# Supplies.net
KiCad netlist of a schematic drawn in Altium Designer
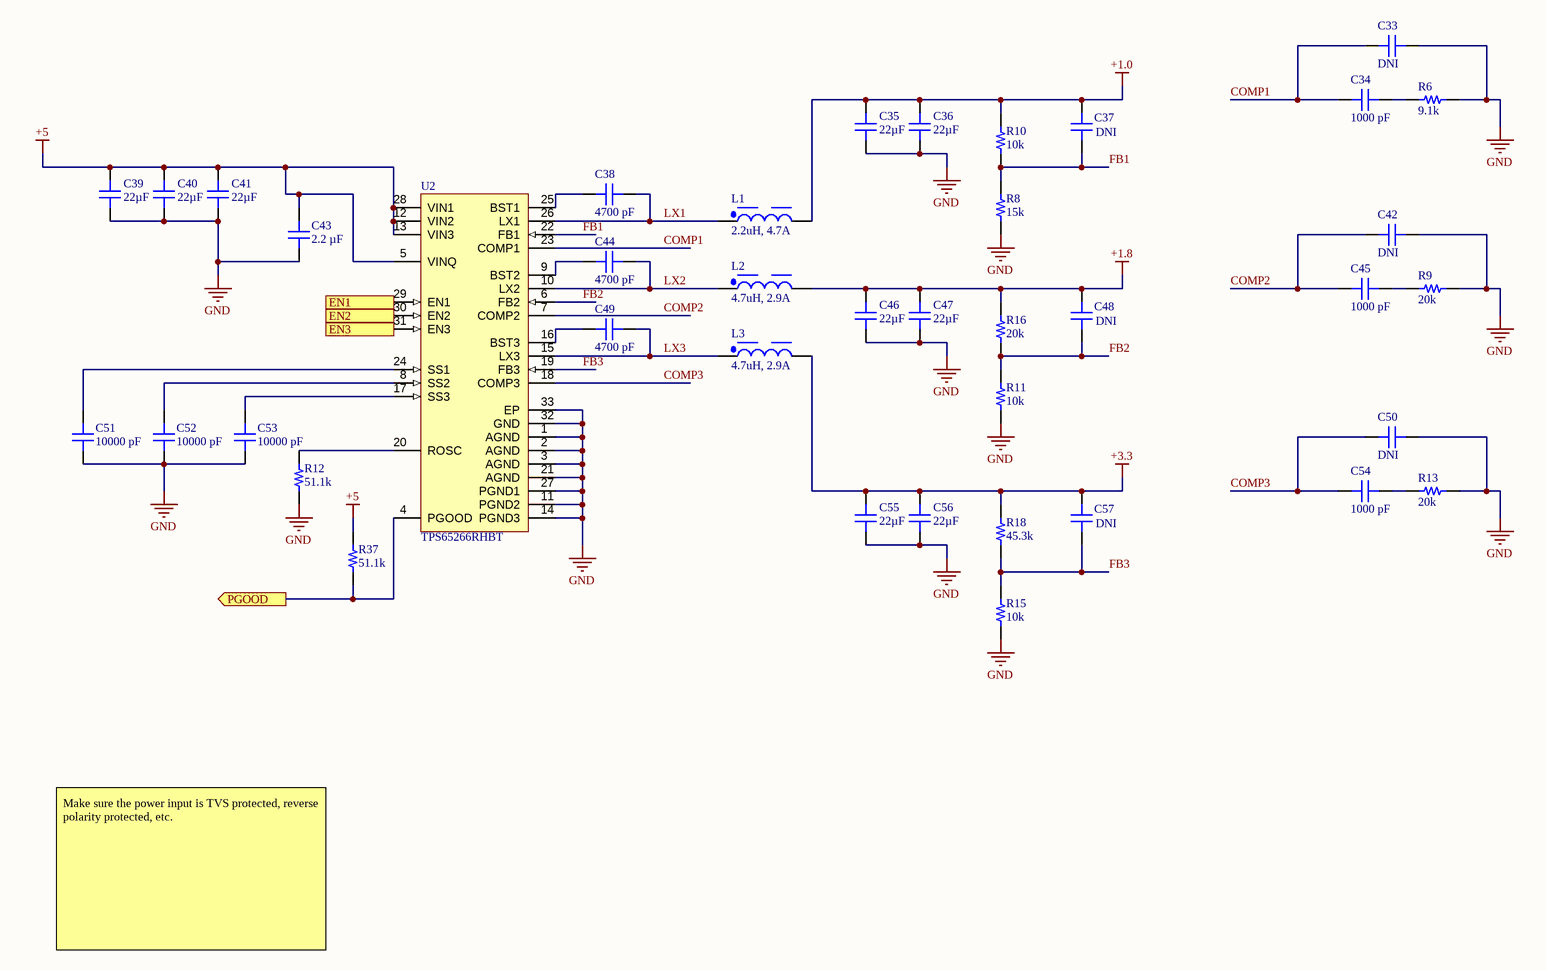
[diagram p0: Supplies.SchDoc]

(export (version "E")
  (design (tool "Eeschema 10.0.6"))
  (components
    (comp (ref "C33")
      (value "DNI")
      (footprint "CAP 0402_1005")
      (libsource (lib "Celestial Altium Library - altium_library") (part "Capacitor"))
    )
    (comp (ref "C34")
      (value "1000 pF")
      (footprint "CAP 0402_1005")
      (description "CAP CER 1000PF 50V C0G/NP0 0402")
      (fields (field (name "PART NUMBER") "C0402C102J5GACAUTO") (field (name "MANUFACTURER") "KEMET"))
      (libsource (lib "Celestial Altium Library - altium_library") (part "Capacitor"))
    )
    (comp (ref "C35")
      (value "22µF")
      (footprint "CAP 0805_2012")
      (description "CAP CER 22UF 10V X5R 0805")
      (fields
        (field (name "PART NUMBER") "GRM21BR61A226ME44L")
        (field (name "MANUFACTURER") "Murata Electronics")
      )
      (libsource (lib "Celestial Altium Library - altium_library") (part "Capacitor"))
    )
    (comp (ref "C36")
      (value "22µF")
      (footprint "CAP 0805_2012")
      (description "CAP CER 22UF 10V X5R 0805")
      (fields
        (field (name "PART NUMBER") "GRM21BR61A226ME44L")
        (field (name "MANUFACTURER") "Murata Electronics")
      )
      (libsource (lib "Celestial Altium Library - altium_library") (part "Capacitor"))
    )
    (comp (ref "C37")
      (value "DNI")
      (footprint "CAP 0402_1005")
      (libsource (lib "Celestial Altium Library - altium_library") (part "Capacitor"))
    )
    (comp (ref "C38")
      (value "4700 pF")
      (footprint "CAP 0201_0603")
      (description "CAP CER 4700PF 16V X7R 0201")
      (fields
        (field (name "PART NUMBER") "GRM033R71C472KE14D")
        (field (name "MANUFACTURER") "Murata Electronics")
      )
      (libsource (lib "Celestial Altium Library - altium_library") (part "Capacitor"))
    )
    (comp (ref "C39")
      (value "22µF")
      (footprint "CAP 0805_2012")
      (description "CAP CER 22UF 10V X5R 0805")
      (fields
        (field (name "PART NUMBER") "GRM21BR61A226ME44L")
        (field (name "MANUFACTURER") "Murata Electronics")
      )
      (libsource (lib "Celestial Altium Library - altium_library") (part "Capacitor"))
    )
    (comp (ref "C40")
      (value "22µF")
      (footprint "CAP 0805_2012")
      (description "CAP CER 22UF 10V X5R 0805")
      (fields
        (field (name "PART NUMBER") "GRM21BR61A226ME44L")
        (field (name "MANUFACTURER") "Murata Electronics")
      )
      (libsource (lib "Celestial Altium Library - altium_library") (part "Capacitor"))
    )
    (comp (ref "C41")
      (value "22µF")
      (footprint "CAP 0805_2012")
      (description "CAP CER 22UF 10V X5R 0805")
      (fields
        (field (name "PART NUMBER") "GRM21BR61A226ME44L")
        (field (name "MANUFACTURER") "Murata Electronics")
      )
      (libsource (lib "Celestial Altium Library - altium_library") (part "Capacitor"))
    )
    (comp (ref "C42")
      (value "DNI")
      (footprint "CAP 0402_1005")
      (libsource (lib "Celestial Altium Library - altium_library") (part "Capacitor"))
    )
    (comp (ref "C43")
      (value "2.2 µF")
      (footprint "CAP 0402_1005")
      (description "CAP CER 2.2UF 16V X5R 0402")
      (fields
        (field (name "PART NUMBER") "GRM155R61C225KE11D")
        (field (name "MANUFACTURER") "Murata Electronics")
      )
      (libsource (lib "Celestial Altium Library - altium_library") (part "Capacitor"))
    )
    (comp (ref "C44")
      (value "4700 pF")
      (footprint "CAP 0201_0603")
      (description "CAP CER 4700PF 16V X7R 0201")
      (fields
        (field (name "PART NUMBER") "GRM033R71C472KE14D")
        (field (name "MANUFACTURER") "Murata Electronics")
      )
      (libsource (lib "Celestial Altium Library - altium_library") (part "Capacitor"))
    )
    (comp (ref "C45")
      (value "1000 pF")
      (footprint "CAP 0402_1005")
      (description "CAP CER 1000PF 50V C0G/NP0 0402")
      (fields (field (name "PART NUMBER") "C0402C102J5GACAUTO") (field (name "MANUFACTURER") "KEMET"))
      (libsource (lib "Celestial Altium Library - altium_library") (part "Capacitor"))
    )
    (comp (ref "C46")
      (value "22µF")
      (footprint "CAP 0805_2012")
      (description "CAP CER 22UF 10V X5R 0805")
      (fields
        (field (name "PART NUMBER") "GRM21BR61A226ME44L")
        (field (name "MANUFACTURER") "Murata Electronics")
      )
      (libsource (lib "Celestial Altium Library - altium_library") (part "Capacitor"))
    )
    (comp (ref "C47")
      (value "22µF")
      (footprint "CAP 0805_2012")
      (description "CAP CER 22UF 10V X5R 0805")
      (fields
        (field (name "PART NUMBER") "GRM21BR61A226ME44L")
        (field (name "MANUFACTURER") "Murata Electronics")
      )
      (libsource (lib "Celestial Altium Library - altium_library") (part "Capacitor"))
    )
    (comp (ref "C48")
      (value "DNI")
      (footprint "CAP 0402_1005")
      (libsource (lib "Celestial Altium Library - altium_library") (part "Capacitor"))
    )
    (comp (ref "C49")
      (value "4700 pF")
      (footprint "CAP 0201_0603")
      (description "CAP CER 4700PF 16V X7R 0201")
      (fields
        (field (name "PART NUMBER") "GRM033R71C472KE14D")
        (field (name "MANUFACTURER") "Murata Electronics")
      )
      (libsource (lib "Celestial Altium Library - altium_library") (part "Capacitor"))
    )
    (comp (ref "C50")
      (value "DNI")
      (footprint "CAP 0402_1005")
      (libsource (lib "Celestial Altium Library - altium_library") (part "Capacitor"))
    )
    (comp (ref "C51")
      (value "10000 pF")
      (footprint "CAP 0402_1005")
      (description "CAP CER 10000PF 50V X7R 0402")
      (fields
        (field (name "PART NUMBER") "GRM155R71H103KA88D")
        (field (name "MANUFACTURER") "Murata Electronics")
      )
      (libsource (lib "Celestial Altium Library - altium_library") (part "Capacitor"))
    )
    (comp (ref "C52")
      (value "10000 pF")
      (footprint "CAP 0402_1005")
      (description "CAP CER 10000PF 50V X7R 0402")
      (fields
        (field (name "PART NUMBER") "GRM155R71H103KA88D")
        (field (name "MANUFACTURER") "Murata Electronics")
      )
      (libsource (lib "Celestial Altium Library - altium_library") (part "Capacitor"))
    )
    (comp (ref "C53")
      (value "10000 pF")
      (footprint "CAP 0402_1005")
      (description "CAP CER 10000PF 50V X7R 0402")
      (fields
        (field (name "PART NUMBER") "GRM155R71H103KA88D")
        (field (name "MANUFACTURER") "Murata Electronics")
      )
      (libsource (lib "Celestial Altium Library - altium_library") (part "Capacitor"))
    )
    (comp (ref "C54")
      (value "1000 pF")
      (footprint "CAP 0402_1005")
      (description "CAP CER 1000PF 50V C0G/NP0 0402")
      (fields (field (name "PART NUMBER") "C0402C102J5GACAUTO") (field (name "MANUFACTURER") "KEMET"))
      (libsource (lib "Celestial Altium Library - altium_library") (part "Capacitor"))
    )
    (comp (ref "C55")
      (value "22µF")
      (footprint "CAP 0805_2012")
      (description "CAP CER 22UF 10V X5R 0805")
      (fields
        (field (name "PART NUMBER") "GRM21BR61A226ME44L")
        (field (name "MANUFACTURER") "Murata Electronics")
      )
      (libsource (lib "Celestial Altium Library - altium_library") (part "Capacitor"))
    )
    (comp (ref "C56")
      (value "22µF")
      (footprint "CAP 0805_2012")
      (description "CAP CER 22UF 10V X5R 0805")
      (fields
        (field (name "PART NUMBER") "GRM21BR61A226ME44L")
        (field (name "MANUFACTURER") "Murata Electronics")
      )
      (libsource (lib "Celestial Altium Library - altium_library") (part "Capacitor"))
    )
    (comp (ref "C57")
      (value "DNI")
      (footprint "CAP 0402_1005")
      (libsource (lib "Celestial Altium Library - altium_library") (part "Capacitor"))
    )
    (comp (ref "L1")
      (value "2.2uH, 4.7A")
      (footprint "WE-MAPI_4020")
      (description "WE-MAPI SMT Power Inductor, size 4020, 2.2uH, 4.7A")
      (fields
        (field (name "MANUFACTURER") "Wurth Elektronik")
        (field (name "MANUFACTURER PART NUMBER") "74438356022")
      )
      (libsource (lib "WE-MAPI (rev22a)") (part "74438356022"))
    )
    (comp (ref "L2")
      (value "4.7uH, 2.9A")
      (footprint "WE-MAPI_4020")
      (description "WE-MAPI SMT Power Inductor, size 4020, 4.7uH, 2.9A")
      (fields
        (field (name "MANUFACTURER") "Wurth Elektronik")
        (field (name "MANUFACTURER PART NUMBER") "74438356047")
      )
      (libsource (lib "WE-MAPI (rev22a)") (part "74438356047"))
    )
    (comp (ref "L3")
      (value "4.7uH, 2.9A")
      (footprint "WE-MAPI_4020")
      (description "WE-MAPI SMT Power Inductor, size 4020, 4.7uH, 2.9A")
      (fields
        (field (name "MANUFACTURER") "Wurth Elektronik")
        (field (name "MANUFACTURER PART NUMBER") "74438356047")
      )
      (libsource (lib "WE-MAPI (rev22a)") (part "74438356047"))
    )
    (comp (ref "R6")
      (value "9.1k")
      (footprint "RES 0402_1005")
      (description "RES SMD 9.1K OHM 1% 1/10W 0402")
      (fields
        (field (name "PART NUMBER") "ERJ-2RKF9101X")
        (field (name "MANUFACTURER") "Panasonic Electronic Components")
      )
      (libsource (lib "Celestial Altium Library - altium_library") (part "Resistor"))
    )
    (comp (ref "R8")
      (value "15k")
      (footprint "RES 0402_1005")
      (description "RES SMD 15K OHM 0.5% 1/16W 0402")
      (fields
        (field (name "PART NUMBER") "ERA-2AED153X")
        (field (name "MANUFACTURER") "Panasonic Electronic Components")
      )
      (libsource (lib "Celestial Altium Library - altium_library") (part "Resistor"))
    )
    (comp (ref "R9")
      (value "20k")
      (footprint "RES 0402_1005")
      (description "RES SMD 20K OHM 0.5% 1/16W 0402")
      (fields
        (field (name "PART NUMBER") "ERA-2AED203X")
        (field (name "MANUFACTURER") "Panasonic Electronic Components")
      )
      (libsource (lib "Celestial Altium Library - altium_library") (part "Resistor"))
    )
    (comp (ref "R10")
      (value "10k")
      (footprint "RES 0402_1005")
      (description "RES SMD 10K OHM 0.5% 1/16W 0402")
      (fields
        (field (name "PART NUMBER") "ERA-2AED103X")
        (field (name "MANUFACTURER") "Panasonic Electronic Components")
      )
      (libsource (lib "Celestial Altium Library - altium_library") (part "Resistor"))
    )
    (comp (ref "R11")
      (value "10k")
      (footprint "RES 0402_1005")
      (description "RES SMD 10K OHM 0.5% 1/16W 0402")
      (fields
        (field (name "PART NUMBER") "ERA-2AED103X")
        (field (name "MANUFACTURER") "Panasonic Electronic Components")
      )
      (libsource (lib "Celestial Altium Library - altium_library") (part "Resistor"))
    )
    (comp (ref "R12")
      (value "51.1k")
      (footprint "RES 0402_1005")
      (description "RES 51.1K OHM 1% 1/10W 0402")
      (fields
        (field (name "PART NUMBER") "RK73H1ETTP5112F")
        (field (name "MANUFACTURER") "KOA Speer Electronics, Inc.")
      )
      (libsource (lib "Celestial Altium Library - altium_library") (part "Resistor"))
    )
    (comp (ref "R13")
      (value "20k")
      (footprint "RES 0402_1005")
      (description "RES SMD 20K OHM 0.5% 1/16W 0402")
      (fields
        (field (name "PART NUMBER") "ERA-2AED203X")
        (field (name "MANUFACTURER") "Panasonic Electronic Components")
      )
      (libsource (lib "Celestial Altium Library - altium_library") (part "Resistor"))
    )
    (comp (ref "R15")
      (value "10k")
      (footprint "RES 0402_1005")
      (description "RES SMD 10K OHM 0.5% 1/16W 0402")
      (fields
        (field (name "PART NUMBER") "ERA-2AED103X")
        (field (name "MANUFACTURER") "Panasonic Electronic Components")
      )
      (libsource (lib "Celestial Altium Library - altium_library") (part "Resistor"))
    )
    (comp (ref "R16")
      (value "20k")
      (footprint "RES 0402_1005")
      (description "RES SMD 20K OHM 0.5% 1/16W 0402")
      (fields
        (field (name "PART NUMBER") "ERA-2AED203X")
        (field (name "MANUFACTURER") "Panasonic Electronic Components")
      )
      (libsource (lib "Celestial Altium Library - altium_library") (part "Resistor"))
    )
    (comp (ref "R18")
      (value "45.3k")
      (footprint "RES 0402_1005")
      (description "RES 45.3K OHM 0.5% 1/16W 0402")
      (fields
        (field (name "PART NUMBER") "RNCF0402DTE45K3")
        (field (name "MANUFACTURER") "Stackpole Electronics Inc")
      )
      (libsource (lib "Celestial Altium Library - altium_library") (part "Resistor"))
    )
    (comp (ref "R37")
      (value "51.1k")
      (footprint "RES 0402_1005")
      (description "RES 51.1K OHM 1% 1/10W 0402")
      (fields
        (field (name "PART NUMBER") "RK73H1ETTP5112F")
        (field (name "MANUFACTURER") "KOA Speer Electronics, Inc.")
      )
      (libsource (lib "Celestial Altium Library - altium_library") (part "Resistor"))
    )
    (comp (ref "U2")
      (value "TPS65266RHBT")
      (footprint "RHB0032E_V")
      (fields (field (name "MANUFACTURER") "TexasInstruments"))
      (libsource (lib "Altium Content Vault") (part "TI-TPS65266-RHB-32"))
    )
  )
  (nets
    (net (code "1") (name "+1.0") (class "Default")
      (node (ref "C35") (pin "1") (pinfunction "1_1") (pintype "passive"))
      (node (ref "C36") (pin "1") (pinfunction "1_1") (pintype "passive"))
      (node (ref "C37") (pin "2") (pinfunction "2_2") (pintype "passive"))
      (node (ref "L1") (pin "2") (pinfunction "2_2") (pintype "passive"))
      (node (ref "R10") (pin "2") (pinfunction "2_2") (pintype "passive"))
    )
    (net (code "2") (name "+1.8") (class "Default")
      (node (ref "C46") (pin "1") (pinfunction "1_1") (pintype "passive"))
      (node (ref "C47") (pin "1") (pinfunction "1_1") (pintype "passive"))
      (node (ref "C48") (pin "2") (pinfunction "2_2") (pintype "passive"))
      (node (ref "L2") (pin "2") (pinfunction "2_2") (pintype "passive"))
      (node (ref "R16") (pin "2") (pinfunction "2_2") (pintype "passive"))
    )
    (net (code "3") (name "+3.3") (class "Default")
      (node (ref "C55") (pin "1") (pinfunction "1_1") (pintype "passive"))
      (node (ref "C56") (pin "1") (pinfunction "1_1") (pintype "passive"))
      (node (ref "C57") (pin "2") (pinfunction "2_2") (pintype "passive"))
      (node (ref "L3") (pin "2") (pinfunction "2_2") (pintype "passive"))
      (node (ref "R18") (pin "2") (pinfunction "2_2") (pintype "passive"))
    )
    (net (code "4") (name "+5") (class "Default")
      (node (ref "C39") (pin "1") (pinfunction "1_1") (pintype "passive"))
      (node (ref "C40") (pin "1") (pinfunction "1_1") (pintype "passive"))
      (node (ref "C41") (pin "1") (pinfunction "1_1") (pintype "passive"))
      (node (ref "C43") (pin "2") (pinfunction "2_2") (pintype "passive"))
      (node (ref "R37") (pin "2") (pinfunction "2_2") (pintype "passive"))
      (node (ref "U2") (pin "12") (pinfunction "VIN2_12") (pintype "power_in"))
      (node (ref "U2") (pin "13") (pinfunction "VIN3_13") (pintype "power_in"))
      (node (ref "U2") (pin "28") (pinfunction "VIN1_28") (pintype "power_in"))
      (node (ref "U2") (pin "5") (pinfunction "VINQ_5") (pintype "power_in"))
    )
    (net (code "5") (name "/COMP1") (class "Default")
      (node (ref "C33") (pin "2") (pinfunction "2_2") (pintype "passive"))
      (node (ref "C34") (pin "2") (pinfunction "2_2") (pintype "passive"))
      (node (ref "U2") (pin "23") (pinfunction "COMP1_23") (pintype "passive"))
    )
    (net (code "6") (name "/COMP2") (class "Default")
      (node (ref "C42") (pin "2") (pinfunction "2_2") (pintype "passive"))
      (node (ref "C45") (pin "2") (pinfunction "2_2") (pintype "passive"))
      (node (ref "U2") (pin "7") (pinfunction "COMP2_7") (pintype "passive"))
    )
    (net (code "7") (name "/COMP3") (class "Default")
      (node (ref "C50") (pin "2") (pinfunction "2_2") (pintype "passive"))
      (node (ref "C54") (pin "2") (pinfunction "2_2") (pintype "passive"))
      (node (ref "U2") (pin "18") (pinfunction "COMP3_18") (pintype "passive"))
    )
    (net (code "8") (name "/EN1") (class "Default")
      (node (ref "U2") (pin "29") (pinfunction "EN1_29") (pintype "input"))
    )
    (net (code "9") (name "/EN2") (class "Default")
      (node (ref "U2") (pin "30") (pinfunction "EN2_30") (pintype "input"))
    )
    (net (code "10") (name "/EN3") (class "Default")
      (node (ref "U2") (pin "31") (pinfunction "EN3_31") (pintype "input"))
    )
    (net (code "11") (name "/FB1") (class "Default")
      (node (ref "C37") (pin "1") (pinfunction "1_1") (pintype "passive"))
      (node (ref "R10") (pin "1") (pinfunction "1_1") (pintype "passive"))
      (node (ref "R8") (pin "2") (pinfunction "2_2") (pintype "passive"))
      (node (ref "U2") (pin "22") (pinfunction "FB1_22") (pintype "input"))
    )
    (net (code "12") (name "/FB2") (class "Default")
      (node (ref "C48") (pin "1") (pinfunction "1_1") (pintype "passive"))
      (node (ref "R11") (pin "2") (pinfunction "2_2") (pintype "passive"))
      (node (ref "R16") (pin "1") (pinfunction "1_1") (pintype "passive"))
      (node (ref "U2") (pin "6") (pinfunction "FB2_6") (pintype "input"))
    )
    (net (code "13") (name "/FB3") (class "Default")
      (node (ref "C57") (pin "1") (pinfunction "1_1") (pintype "passive"))
      (node (ref "R15") (pin "2") (pinfunction "2_2") (pintype "passive"))
      (node (ref "R18") (pin "1") (pinfunction "1_1") (pintype "passive"))
      (node (ref "U2") (pin "19") (pinfunction "FB3_19") (pintype "input"))
    )
    (net (code "14") (name "/LX1") (class "Default")
      (node (ref "C38") (pin "2") (pinfunction "2_2") (pintype "passive"))
      (node (ref "L1") (pin "1") (pinfunction "1_1") (pintype "passive"))
      (node (ref "U2") (pin "26") (pinfunction "LX1_26") (pintype "passive"))
    )
    (net (code "15") (name "/LX2") (class "Default")
      (node (ref "C44") (pin "2") (pinfunction "2_2") (pintype "passive"))
      (node (ref "L2") (pin "1") (pinfunction "1_1") (pintype "passive"))
      (node (ref "U2") (pin "10") (pinfunction "LX2_10") (pintype "passive"))
    )
    (net (code "16") (name "/LX3") (class "Default")
      (node (ref "C49") (pin "2") (pinfunction "2_2") (pintype "passive"))
      (node (ref "L3") (pin "1") (pinfunction "1_1") (pintype "passive"))
      (node (ref "U2") (pin "15") (pinfunction "LX3_15") (pintype "passive"))
    )
    (net (code "17") (name "/PGOOD") (class "Default")
      (node (ref "R37") (pin "1") (pinfunction "1_1") (pintype "passive"))
      (node (ref "U2") (pin "4") (pinfunction "PGOOD_4") (pintype "open_collector"))
    )
    (net (code "18") (name "GND") (class "Default")
      (node (ref "C33") (pin "1") (pinfunction "1_1") (pintype "passive"))
      (node (ref "C35") (pin "2") (pinfunction "2_2") (pintype "passive"))
      (node (ref "C36") (pin "2") (pinfunction "2_2") (pintype "passive"))
      (node (ref "C39") (pin "2") (pinfunction "2_2") (pintype "passive"))
      (node (ref "C40") (pin "2") (pinfunction "2_2") (pintype "passive"))
      (node (ref "C41") (pin "2") (pinfunction "2_2") (pintype "passive"))
      (node (ref "C42") (pin "1") (pinfunction "1_1") (pintype "passive"))
      (node (ref "C43") (pin "1") (pinfunction "1_1") (pintype "passive"))
      (node (ref "C46") (pin "2") (pinfunction "2_2") (pintype "passive"))
      (node (ref "C47") (pin "2") (pinfunction "2_2") (pintype "passive"))
      (node (ref "C50") (pin "1") (pinfunction "1_1") (pintype "passive"))
      (node (ref "C51") (pin "1") (pinfunction "1_1") (pintype "passive"))
      (node (ref "C52") (pin "1") (pinfunction "1_1") (pintype "passive"))
      (node (ref "C53") (pin "1") (pinfunction "1_1") (pintype "passive"))
      (node (ref "C55") (pin "2") (pinfunction "2_2") (pintype "passive"))
      (node (ref "C56") (pin "2") (pinfunction "2_2") (pintype "passive"))
      (node (ref "R11") (pin "1") (pinfunction "1_1") (pintype "passive"))
      (node (ref "R12") (pin "1") (pinfunction "1_1") (pintype "passive"))
      (node (ref "R13") (pin "1") (pinfunction "1_1") (pintype "passive"))
      (node (ref "R15") (pin "1") (pinfunction "1_1") (pintype "passive"))
      (node (ref "R6") (pin "2") (pinfunction "2_2") (pintype "passive"))
      (node (ref "R8") (pin "1") (pinfunction "1_1") (pintype "passive"))
      (node (ref "R9") (pin "2") (pinfunction "2_2") (pintype "passive"))
      (node (ref "U2") (pin "1") (pinfunction "AGND_1") (pintype "power_in"))
      (node (ref "U2") (pin "11") (pinfunction "PGND2_11") (pintype "power_in"))
      (node (ref "U2") (pin "14") (pinfunction "PGND3_14") (pintype "power_in"))
      (node (ref "U2") (pin "2") (pinfunction "AGND_2") (pintype "power_in"))
      (node (ref "U2") (pin "21") (pinfunction "AGND_21") (pintype "power_in"))
      (node (ref "U2") (pin "27") (pinfunction "PGND1_27") (pintype "power_in"))
      (node (ref "U2") (pin "3") (pinfunction "AGND_3") (pintype "power_in"))
      (node (ref "U2") (pin "32") (pinfunction "GND_32") (pintype "power_in"))
      (node (ref "U2") (pin "33") (pinfunction "EP_33") (pintype "power_in"))
    )
    (net (code "19") (name "Net-(C34-Pad1)") (class "Default")
      (node (ref "C34") (pin "1") (pinfunction "1_1") (pintype "passive"))
      (node (ref "R6") (pin "1") (pinfunction "1_1") (pintype "passive"))
    )
    (net (code "20") (name "Net-(C45-Pad1)") (class "Default")
      (node (ref "C45") (pin "1") (pinfunction "1_1") (pintype "passive"))
      (node (ref "R9") (pin "1") (pinfunction "1_1") (pintype "passive"))
    )
    (net (code "21") (name "Net-(C54-Pad1)") (class "Default")
      (node (ref "C54") (pin "1") (pinfunction "1_1") (pintype "passive"))
      (node (ref "R13") (pin "2") (pinfunction "2_2") (pintype "passive"))
    )
    (net (code "22") (name "Net-(U2-BST1)") (class "Default")
      (node (ref "C38") (pin "1") (pinfunction "1_1") (pintype "passive"))
      (node (ref "U2") (pin "25") (pinfunction "BST1_25") (pintype "power_in"))
    )
    (net (code "23") (name "Net-(U2-BST2)") (class "Default")
      (node (ref "C44") (pin "1") (pinfunction "1_1") (pintype "passive"))
      (node (ref "U2") (pin "9") (pinfunction "BST2_9") (pintype "power_in"))
    )
    (net (code "24") (name "Net-(U2-BST3)") (class "Default")
      (node (ref "C49") (pin "1") (pinfunction "1_1") (pintype "passive"))
      (node (ref "U2") (pin "16") (pinfunction "BST3_16") (pintype "power_in"))
    )
    (net (code "25") (name "Net-(U2-ROSC)") (class "Default")
      (node (ref "R12") (pin "2") (pinfunction "2_2") (pintype "passive"))
      (node (ref "U2") (pin "20") (pinfunction "ROSC_20") (pintype "passive"))
    )
    (net (code "26") (name "Net-(U2-SS1)") (class "Default")
      (node (ref "C51") (pin "2") (pinfunction "2_2") (pintype "passive"))
      (node (ref "U2") (pin "24") (pinfunction "SS1_24") (pintype "input"))
    )
    (net (code "27") (name "Net-(U2-SS2)") (class "Default")
      (node (ref "C52") (pin "2") (pinfunction "2_2") (pintype "passive"))
      (node (ref "U2") (pin "8") (pinfunction "SS2_8") (pintype "input"))
    )
    (net (code "28") (name "Net-(U2-SS3)") (class "Default")
      (node (ref "C53") (pin "2") (pinfunction "2_2") (pintype "passive"))
      (node (ref "U2") (pin "17") (pinfunction "SS3_17") (pintype "input"))
    )
  )
)
